# BMS_Rev_1.net
KiCad netlist of a schematic drawn in EAGLE
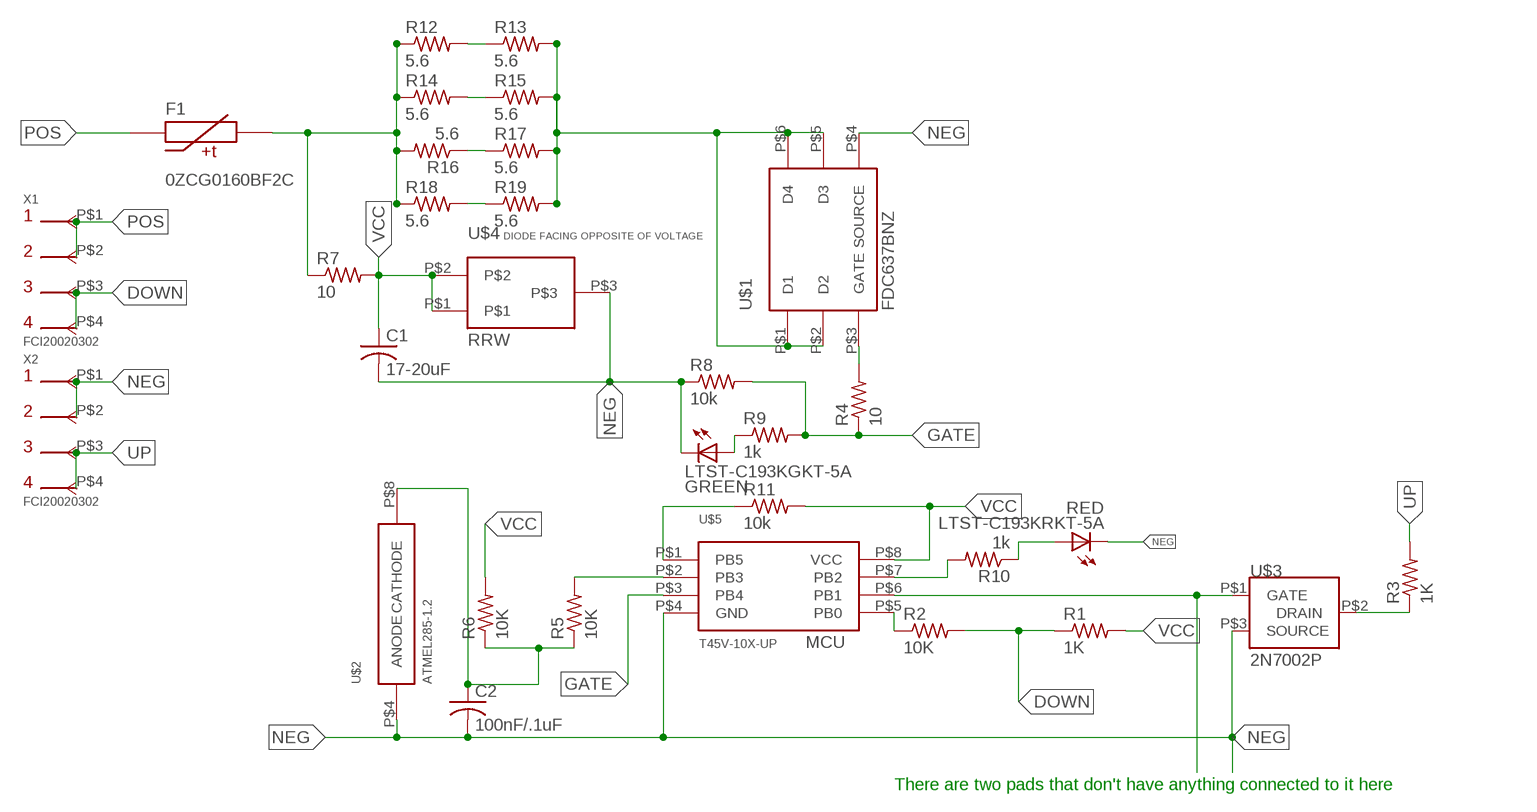
[diagram p0: schematic, sheet 1]

(export (version "E")
  (design (tool "Eeschema 10.0.6"))
  (components
    (comp (ref "C1")
      (value "17-20uF")
      (footprint "eagle-import:C0805")
      (libsource (lib "eagle-import") (part "C-USC0805"))
    )
    (comp (ref "C2")
      (value "100nF/.1uF")
      (footprint "eagle-import:C0805")
      (libsource (lib "eagle-import") (part "C-USC0805"))
    )
    (comp (ref "F1")
      (value "0ZCG0160BF2C")
      (footprint "eagle-import:1812")
      (libsource (lib "eagle-import") (part "0ZCG0160BF2C"))
    )
    (comp (ref "LTST-C193KGKT-5A")
      (value "GREEN")
      (footprint "eagle-import:CHIPLED_1206")
      (libsource (lib "eagle-import") (part "LEDCHIPLED_1206"))
    )
    (comp (ref "LTST-C193KRKT-5A")
      (value "RED")
      (footprint "eagle-import:CHIPLED_1206")
      (libsource (lib "eagle-import") (part "LEDCHIPLED_1206"))
    )
    (comp (ref "R1")
      (value "1K")
      (footprint "eagle-import:R0805")
      (libsource (lib "eagle-import") (part "resistor_R-US_R0805"))
    )
    (comp (ref "R2")
      (value "10K")
      (footprint "eagle-import:R0805")
      (libsource (lib "eagle-import") (part "resistor_R-US_R0805"))
    )
    (comp (ref "R3")
      (value "1K")
      (footprint "eagle-import:R0805")
      (libsource (lib "eagle-import") (part "resistor_R-US_R0805"))
    )
    (comp (ref "R4")
      (value "10")
      (footprint "eagle-import:R0805")
      (libsource (lib "eagle-import") (part "resistor_R-US_R0805"))
    )
    (comp (ref "R5")
      (value "10K")
      (footprint "eagle-import:R0805")
      (libsource (lib "eagle-import") (part "resistor_R-US_R0805"))
    )
    (comp (ref "R6")
      (value "10K")
      (footprint "eagle-import:R0805")
      (libsource (lib "eagle-import") (part "resistor_R-US_R0805"))
    )
    (comp (ref "R7")
      (value "10")
      (footprint "eagle-import:R0805")
      (libsource (lib "eagle-import") (part "resistor_R-US_R0805"))
    )
    (comp (ref "R8")
      (value "10k")
      (footprint "eagle-import:R0805")
      (libsource (lib "eagle-import") (part "resistor_R-US_R0805"))
    )
    (comp (ref "R9")
      (value "1k")
      (footprint "eagle-import:R0805")
      (libsource (lib "eagle-import") (part "resistor_R-US_R0805"))
    )
    (comp (ref "R10")
      (value "1k")
      (footprint "eagle-import:R0805")
      (libsource (lib "eagle-import") (part "resistor_R-US_R0805"))
    )
    (comp (ref "R11")
      (value "10k")
      (footprint "eagle-import:R0805")
      (libsource (lib "eagle-import") (part "resistor_R-US_R0805"))
    )
    (comp (ref "R12")
      (value "5.6")
      (footprint "eagle-import:R1206")
      (libsource (lib "eagle-import") (part "R-US_R1206"))
    )
    (comp (ref "R13")
      (value "5.6")
      (footprint "eagle-import:R1206")
      (libsource (lib "eagle-import") (part "R-US_R1206"))
    )
    (comp (ref "R14")
      (value "5.6")
      (footprint "eagle-import:R1206")
      (libsource (lib "eagle-import") (part "R-US_R1206"))
    )
    (comp (ref "R15")
      (value "5.6")
      (footprint "eagle-import:R1206")
      (libsource (lib "eagle-import") (part "R-US_R1206"))
    )
    (comp (ref "R16")
      (value "5.6")
      (footprint "eagle-import:R1206")
      (libsource (lib "eagle-import") (part "R-US_R1206"))
    )
    (comp (ref "R17")
      (value "5.6")
      (footprint "eagle-import:R1206")
      (libsource (lib "eagle-import") (part "R-US_R1206"))
    )
    (comp (ref "R18")
      (value "5.6")
      (footprint "eagle-import:R1206")
      (libsource (lib "eagle-import") (part "R-US_R1206"))
    )
    (comp (ref "R19")
      (value "5.6")
      (footprint "eagle-import:R1206")
      (libsource (lib "eagle-import") (part "R-US_R1206"))
    )
    (comp (ref "U$1")
      (value "FDC637BNZ")
      (footprint "eagle-import:SOT-23-6")
      (libsource (lib "eagle-import") (part "FDC637BNZ"))
    )
    (comp (ref "U$2")
      (value "ATMEL285-1.2")
      (footprint "eagle-import:8-SOIC")
      (libsource (lib "eagle-import") (part "ATMEL285-1.2"))
    )
    (comp (ref "U$3")
      (value "2N7002P")
      (footprint "eagle-import:SOT23-3")
      (libsource (lib "eagle-import") (part "2N7002P"))
    )
    (comp (ref "U$4")
      (value "RRW")
      (footprint "eagle-import:SOT23-3")
      (libsource (lib "eagle-import") (part "RRW"))
    )
    (comp (ref "U$5")
      (value "T45V-10X-UP")
      (footprint "eagle-import:TSSOP-8(ATMEL)")
      (libsource (lib "eagle-import") (part "T45V-10X-UP"))
    )
    (comp (ref "X1")
      (value "FCI20020302")
      (footprint "eagle-import:2_PIN_AMPHENOL")
      (libsource (lib "eagle-import") (part "FCI20020302"))
    )
    (comp (ref "X2")
      (value "FCI20020302")
      (footprint "eagle-import:2_PIN_AMPHENOL")
      (libsource (lib "eagle-import") (part "FCI20020302"))
    )
  )
  (nets
    (net (code "1") (name "DOWN") (class "Default")
      (node (ref "R1") (pin "1") (pinfunction "1_1") (pintype "passive"))
      (node (ref "R2") (pin "2") (pinfunction "2_2") (pintype "passive"))
      (node (ref "X1") (pin "P$3") (pinfunction "P$3_P$3") (pintype "bidirectional"))
      (node (ref "X1") (pin "P$4") (pinfunction "P$4_P$4") (pintype "bidirectional"))
    )
    (net (code "2") (name "GATE") (class "Default")
      (node (ref "R4") (pin "1") (pinfunction "1_1") (pintype "passive"))
      (node (ref "R8") (pin "2") (pinfunction "2_2") (pintype "passive"))
      (node (ref "R9") (pin "2") (pinfunction "2_2") (pintype "passive"))
      (node (ref "U$5") (pin "P$3") (pinfunction "PB4_P$3") (pintype "bidirectional"))
    )
    (net (code "3") (name "NEG") (class "Default")
      (node (ref "C1") (pin "2") (pinfunction "2_2") (pintype "passive"))
      (node (ref "C2") (pin "2") (pinfunction "2_2") (pintype "passive"))
      (node (ref "LTST-C193KGKT-5A") (pin "C") (pinfunction "C_C") (pintype "passive"))
      (node (ref "LTST-C193KRKT-5A") (pin "C") (pinfunction "C_C") (pintype "passive"))
      (node (ref "R8") (pin "1") (pinfunction "1_1") (pintype "passive"))
      (node (ref "U$1") (pin "P$4") (pinfunction "SOURCE_P$4") (pintype "bidirectional"))
      (node (ref "U$2") (pin "P$4") (pinfunction "ANODE_P$4") (pintype "bidirectional"))
      (node (ref "U$3") (pin "P$3") (pinfunction "SOURCE_P$3") (pintype "bidirectional"))
      (node (ref "U$4") (pin "P$3") (pinfunction "P$3_P$3") (pintype "bidirectional"))
      (node (ref "U$5") (pin "P$4") (pinfunction "GND_P$4") (pintype "bidirectional"))
      (node (ref "X2") (pin "P$1") (pinfunction "P$1_P$1") (pintype "bidirectional"))
      (node (ref "X2") (pin "P$2") (pinfunction "P$2_P$2") (pintype "bidirectional"))
    )
    (net (code "4") (name "Net-(F1-PadP$2)") (class "Default")
      (node (ref "F1") (pin "P$2") (pinfunction "P$2_P$2") (pintype "bidirectional"))
      (node (ref "R12") (pin "1") (pinfunction "1_1") (pintype "passive"))
      (node (ref "R14") (pin "1") (pinfunction "1_1") (pintype "passive"))
      (node (ref "R16") (pin "2") (pinfunction "2_2") (pintype "passive"))
      (node (ref "R18") (pin "1") (pinfunction "1_1") (pintype "passive"))
      (node (ref "R7") (pin "1") (pinfunction "1_1") (pintype "passive"))
    )
    (net (code "5") (name "Net-(LTST-C193KGKT-5A-PadA)") (class "Default")
      (node (ref "LTST-C193KGKT-5A") (pin "A") (pinfunction "A_A") (pintype "passive"))
      (node (ref "R9") (pin "1") (pinfunction "1_1") (pintype "passive"))
    )
    (net (code "6") (name "Net-(LTST-C193KRKT-5A-PadA)") (class "Default")
      (node (ref "LTST-C193KRKT-5A") (pin "A") (pinfunction "A_A") (pintype "passive"))
      (node (ref "R10") (pin "1") (pinfunction "1_1") (pintype "passive"))
    )
    (net (code "7") (name "Net-(R12-Pad2)") (class "Default")
      (node (ref "R12") (pin "2") (pinfunction "2_2") (pintype "passive"))
      (node (ref "R13") (pin "1") (pinfunction "1_1") (pintype "passive"))
    )
    (net (code "8") (name "Net-(R14-Pad2)") (class "Default")
      (node (ref "R14") (pin "2") (pinfunction "2_2") (pintype "passive"))
      (node (ref "R15") (pin "1") (pinfunction "1_1") (pintype "passive"))
    )
    (net (code "9") (name "Net-(R16-Pad1)") (class "Default")
      (node (ref "R16") (pin "1") (pinfunction "1_1") (pintype "passive"))
      (node (ref "R17") (pin "1") (pinfunction "1_1") (pintype "passive"))
    )
    (net (code "10") (name "Net-(R18-Pad2)") (class "Default")
      (node (ref "R18") (pin "2") (pinfunction "2_2") (pintype "passive"))
      (node (ref "R19") (pin "1") (pinfunction "1_1") (pintype "passive"))
    )
    (net (code "11") (name "Net-(U$1-D1)") (class "Default")
      (node (ref "R13") (pin "2") (pinfunction "2_2") (pintype "passive"))
      (node (ref "R15") (pin "2") (pinfunction "2_2") (pintype "passive"))
      (node (ref "R17") (pin "2") (pinfunction "2_2") (pintype "passive"))
      (node (ref "R19") (pin "2") (pinfunction "2_2") (pintype "passive"))
      (node (ref "U$1") (pin "P$1") (pinfunction "D1_P$1") (pintype "bidirectional"))
      (node (ref "U$1") (pin "P$2") (pinfunction "D2_P$2") (pintype "bidirectional"))
      (node (ref "U$1") (pin "P$5") (pinfunction "D3_P$5") (pintype "bidirectional"))
      (node (ref "U$1") (pin "P$6") (pinfunction "D4_P$6") (pintype "bidirectional"))
    )
    (net (code "12") (name "Net-(U$1-GATE)") (class "Default")
      (node (ref "R4") (pin "2") (pinfunction "2_2") (pintype "passive"))
      (node (ref "U$1") (pin "P$3") (pinfunction "GATE_P$3") (pintype "bidirectional"))
    )
    (net (code "13") (name "Net-(U$2-CATHODE)") (class "Default")
      (node (ref "C2") (pin "1") (pinfunction "1_1") (pintype "passive"))
      (node (ref "R5") (pin "1") (pinfunction "1_1") (pintype "passive"))
      (node (ref "R6") (pin "1") (pinfunction "1_1") (pintype "passive"))
      (node (ref "U$2") (pin "P$8") (pinfunction "CATHODE_P$8") (pintype "bidirectional"))
    )
    (net (code "14") (name "Net-(U$3-DRAIN)") (class "Default")
      (node (ref "R3") (pin "1") (pinfunction "1_1") (pintype "passive"))
      (node (ref "U$3") (pin "P$2") (pinfunction "DRAIN_P$2") (pintype "bidirectional"))
    )
    (net (code "15") (name "Net-(U$3-GATE)") (class "Default")
      (node (ref "U$3") (pin "P$1") (pinfunction "GATE_P$1") (pintype "bidirectional"))
      (node (ref "U$5") (pin "P$6") (pinfunction "PB1_P$6") (pintype "bidirectional"))
    )
    (net (code "16") (name "Net-(U$5-PB0)") (class "Default")
      (node (ref "R2") (pin "1") (pinfunction "1_1") (pintype "passive"))
      (node (ref "U$5") (pin "P$5") (pinfunction "PB0_P$5") (pintype "bidirectional"))
    )
    (net (code "17") (name "Net-(U$5-PB2)") (class "Default")
      (node (ref "R10") (pin "2") (pinfunction "2_2") (pintype "passive"))
      (node (ref "U$5") (pin "P$7") (pinfunction "PB2_P$7") (pintype "bidirectional"))
    )
    (net (code "18") (name "Net-(U$5-PB3)") (class "Default")
      (node (ref "R5") (pin "2") (pinfunction "2_2") (pintype "passive"))
      (node (ref "U$5") (pin "P$2") (pinfunction "PB3_P$2") (pintype "bidirectional"))
    )
    (net (code "19") (name "Net-(U$5-PB5)") (class "Default")
      (node (ref "R11") (pin "1") (pinfunction "1_1") (pintype "passive"))
      (node (ref "U$5") (pin "P$1") (pinfunction "PB5_P$1") (pintype "bidirectional"))
    )
    (net (code "20") (name "POS") (class "Default")
      (node (ref "F1") (pin "P$1") (pinfunction "P$1_P$1") (pintype "bidirectional"))
      (node (ref "X1") (pin "P$1") (pinfunction "P$1_P$1") (pintype "bidirectional"))
      (node (ref "X1") (pin "P$2") (pinfunction "P$2_P$2") (pintype "bidirectional"))
    )
    (net (code "21") (name "UP") (class "Default")
      (node (ref "R3") (pin "2") (pinfunction "2_2") (pintype "passive"))
      (node (ref "X2") (pin "P$3") (pinfunction "P$3_P$3") (pintype "bidirectional"))
      (node (ref "X2") (pin "P$4") (pinfunction "P$4_P$4") (pintype "bidirectional"))
    )
    (net (code "22") (name "VCC") (class "Default")
      (node (ref "C1") (pin "1") (pinfunction "1_1") (pintype "passive"))
      (node (ref "R1") (pin "2") (pinfunction "2_2") (pintype "passive"))
      (node (ref "R11") (pin "2") (pinfunction "2_2") (pintype "passive"))
      (node (ref "R6") (pin "2") (pinfunction "2_2") (pintype "passive"))
      (node (ref "R7") (pin "2") (pinfunction "2_2") (pintype "passive"))
      (node (ref "U$4") (pin "P$1") (pinfunction "P$1_P$1") (pintype "bidirectional"))
      (node (ref "U$4") (pin "P$2") (pinfunction "P$2_P$2") (pintype "bidirectional"))
      (node (ref "U$5") (pin "P$8") (pinfunction "VCC_P$8") (pintype "bidirectional"))
    )
  )
)
